# XMOD.net
KiCad netlist of a schematic drawn in Altium Designer
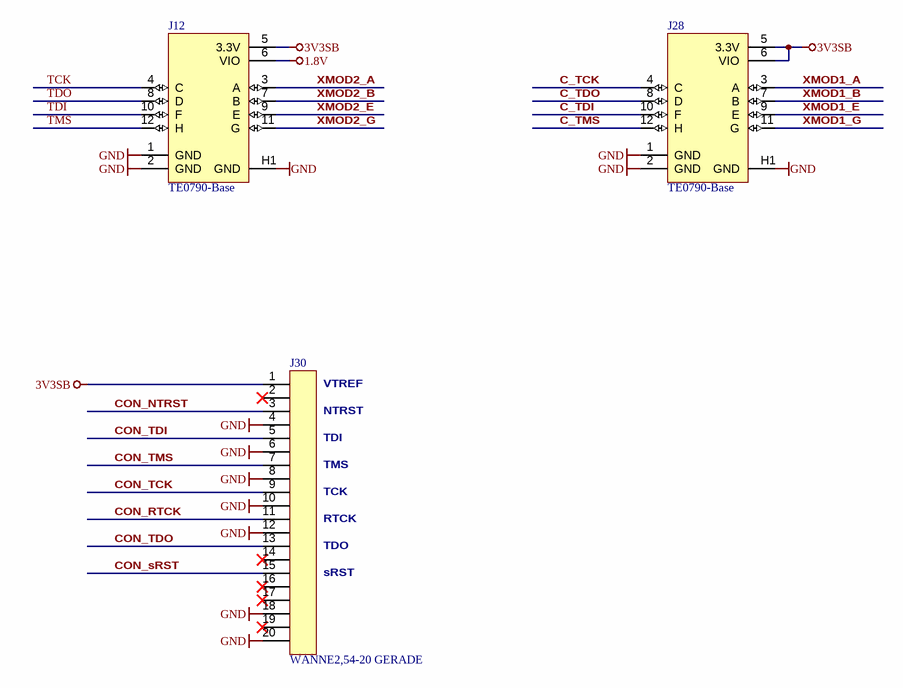
[diagram p0: XMOD.schdoc]

(export (version "E")
  (design (tool "Eeschema 10.0.6"))
  (components
    (comp (ref "J12")
      (value "TE0790-Base")
      (footprint "TE0790-Base")
      (libsource (lib "TE") (part "TE0790-JB"))
    )
    (comp (ref "J28")
      (value "TE0790-Base")
      (footprint "TE0790-Base")
      (libsource (lib "TE") (part "TE0790-JB"))
    )
    (comp (ref "J30")
      (value "WANNE2,54-20 GERADE")
      (footprint "WANNE2,54-20 GERADE")
      (description "Stiftleiste Wanne 20polig")
      (libsource (lib "TE") (part "CON-20"))
    )
  )
  (nets
    (net (code "1") (name "/CON_NTRST") (class "Default")
      (node (ref "J30") (pin "3") (pinfunction "3_3") (pintype "passive"))
    )
    (net (code "2") (name "/CON_RTCK") (class "Default")
      (node (ref "J30") (pin "11") (pinfunction "11_11") (pintype "passive"))
    )
    (net (code "3") (name "/CON_TCK") (class "Default")
      (node (ref "J30") (pin "9") (pinfunction "9_9") (pintype "passive"))
    )
    (net (code "4") (name "/CON_TDI") (class "Default")
      (node (ref "J30") (pin "5") (pinfunction "5_5") (pintype "passive"))
    )
    (net (code "5") (name "/CON_TDO") (class "Default")
      (node (ref "J30") (pin "13") (pinfunction "13_13") (pintype "passive"))
    )
    (net (code "6") (name "/CON_TMS") (class "Default")
      (node (ref "J30") (pin "7") (pinfunction "7_7") (pintype "passive"))
    )
    (net (code "7") (name "/CON_sRST") (class "Default")
      (node (ref "J30") (pin "15") (pinfunction "15_15") (pintype "passive"))
    )
    (net (code "8") (name "/C_TCK") (class "Default")
      (node (ref "J28") (pin "4") (pinfunction "C_4") (pintype "bidirectional"))
    )
    (net (code "9") (name "/C_TDI") (class "Default")
      (node (ref "J28") (pin "10") (pinfunction "F_10") (pintype "bidirectional"))
    )
    (net (code "10") (name "/C_TDO") (class "Default")
      (node (ref "J28") (pin "8") (pinfunction "D_8") (pintype "bidirectional"))
    )
    (net (code "11") (name "/C_TMS") (class "Default")
      (node (ref "J28") (pin "12") (pinfunction "H_12") (pintype "bidirectional"))
    )
    (net (code "12") (name "/TCK") (class "Default")
      (node (ref "J12") (pin "4") (pinfunction "C_4") (pintype "bidirectional"))
    )
    (net (code "13") (name "/TDI") (class "Default")
      (node (ref "J12") (pin "10") (pinfunction "F_10") (pintype "bidirectional"))
    )
    (net (code "14") (name "/TDO") (class "Default")
      (node (ref "J12") (pin "8") (pinfunction "D_8") (pintype "bidirectional"))
    )
    (net (code "15") (name "/TMS") (class "Default")
      (node (ref "J12") (pin "12") (pinfunction "H_12") (pintype "bidirectional"))
    )
    (net (code "16") (name "/XMOD1_A") (class "Default")
      (node (ref "J28") (pin "3") (pinfunction "A_3") (pintype "bidirectional"))
    )
    (net (code "17") (name "/XMOD1_B") (class "Default")
      (node (ref "J28") (pin "7") (pinfunction "B_7") (pintype "bidirectional"))
    )
    (net (code "18") (name "/XMOD1_E") (class "Default")
      (node (ref "J28") (pin "9") (pinfunction "E_9") (pintype "bidirectional"))
    )
    (net (code "19") (name "/XMOD1_G") (class "Default")
      (node (ref "J28") (pin "11") (pinfunction "G_11") (pintype "bidirectional"))
    )
    (net (code "20") (name "/XMOD2_A") (class "Default")
      (node (ref "J12") (pin "3") (pinfunction "A_3") (pintype "bidirectional"))
    )
    (net (code "21") (name "/XMOD2_B") (class "Default")
      (node (ref "J12") (pin "7") (pinfunction "B_7") (pintype "bidirectional"))
    )
    (net (code "22") (name "/XMOD2_E") (class "Default")
      (node (ref "J12") (pin "9") (pinfunction "E_9") (pintype "bidirectional"))
    )
    (net (code "23") (name "/XMOD2_G") (class "Default")
      (node (ref "J12") (pin "11") (pinfunction "G_11") (pintype "bidirectional"))
    )
    (net (code "24") (name "1.8V") (class "Default")
      (node (ref "J12") (pin "6") (pinfunction "VIO_6") (pintype "power_in"))
    )
    (net (code "25") (name "3V3SB") (class "Default")
      (node (ref "J12") (pin "5") (pinfunction "3.3V_5") (pintype "power_in"))
      (node (ref "J28") (pin "5") (pinfunction "3.3V_5") (pintype "power_in"))
      (node (ref "J28") (pin "6") (pinfunction "VIO_6") (pintype "power_in"))
      (node (ref "J30") (pin "1") (pinfunction "1_1") (pintype "passive"))
    )
    (net (code "26") (name "GND") (class "Default")
      (node (ref "J12") (pin "1") (pinfunction "GND_1") (pintype "power_in"))
      (node (ref "J12") (pin "2") (pinfunction "GND_2") (pintype "power_in"))
      (node (ref "J12") (pin "H1") (pinfunction "GND_H1") (pintype "power_in"))
      (node (ref "J28") (pin "1") (pinfunction "GND_1") (pintype "power_in"))
      (node (ref "J28") (pin "2") (pinfunction "GND_2") (pintype "power_in"))
      (node (ref "J28") (pin "H1") (pinfunction "GND_H1") (pintype "power_in"))
      (node (ref "J30") (pin "10") (pinfunction "10_10") (pintype "passive"))
      (node (ref "J30") (pin "12") (pinfunction "12_12") (pintype "passive"))
      (node (ref "J30") (pin "18") (pinfunction "18_18") (pintype "passive"))
      (node (ref "J30") (pin "20") (pinfunction "20_20") (pintype "passive"))
      (node (ref "J30") (pin "4") (pinfunction "4_4") (pintype "passive"))
      (node (ref "J30") (pin "6") (pinfunction "6_6") (pintype "passive"))
      (node (ref "J30") (pin "8") (pinfunction "8_8") (pintype "passive"))
    )
    (net (code "27") (name "unconnected-(J30-Pad2)") (class "Default")
      (node (ref "J30") (pin "2") (pinfunction "2_2") (pintype "passive+no_connect"))
    )
    (net (code "28") (name "unconnected-(J30-Pad14)") (class "Default")
      (node (ref "J30") (pin "14") (pinfunction "14_14") (pintype "passive+no_connect"))
    )
    (net (code "29") (name "unconnected-(J30-Pad16)") (class "Default")
      (node (ref "J30") (pin "16") (pinfunction "16_16") (pintype "passive+no_connect"))
    )
    (net (code "30") (name "unconnected-(J30-Pad17)") (class "Default")
      (node (ref "J30") (pin "17") (pinfunction "17_17") (pintype "passive+no_connect"))
    )
    (net (code "31") (name "unconnected-(J30-Pad19)") (class "Default")
      (node (ref "J30") (pin "19") (pinfunction "19_19") (pintype "passive+no_connect"))
    )
  )
)
